# RS_232.net
KiCad netlist of a schematic drawn in Altium Designer
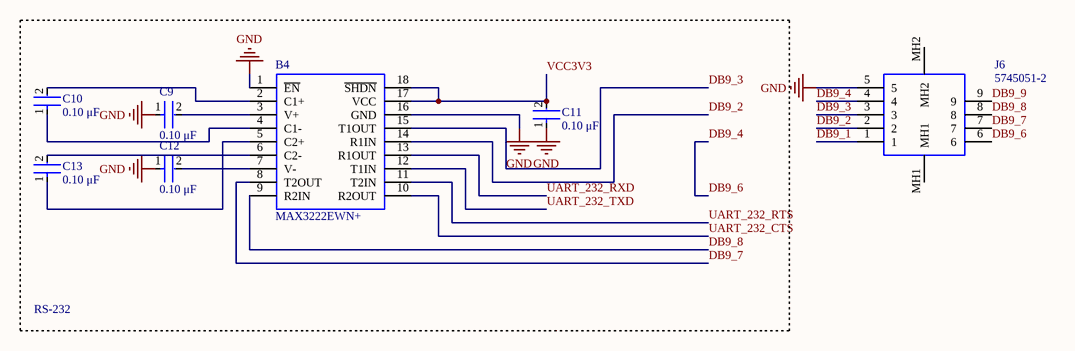
[diagram p0: RS_232.SchDoc]

(export (version "E")
  (design (tool "Eeschema 10.0.6"))
  (components
    (comp (ref "B4")
      (value "MAX3222EWN+")
      (footprint "SOIC127P1032X265-18N")
      (fields (field (name "MOUSER PART NUMBER") "700-MAX3222EWN"))
      (libsource (lib "Schlib2") (part "MAX3222EWN+"))
    )
    (comp (ref "C9")
      (value "0.10 μF")
      (footprint "FP-C0805C-DN-MFG")
      (description "C0805 0.10 μF X7R 30ppm/°C 10.00% 50 V")
      (fields
        (field (name "MANUFACTURER") "KEMET")
        (field (name "MANUFACTURER PART NUMBER") "C0805C104K5RAC7411")
      )
      (libsource (lib "Altium Content Vault") (part "b4654b650e69147ec39a6b967a45e02"))
    )
    (comp (ref "C10")
      (value "0.10 μF")
      (footprint "FP-C0805C-DN-MFG")
      (description "C0805 0.10 μF X7R 30ppm/°C 10.00% 50 V")
      (fields
        (field (name "MANUFACTURER") "KEMET")
        (field (name "MANUFACTURER PART NUMBER") "C0805C104K5RAC7411")
      )
      (libsource (lib "Altium Content Vault") (part "b4654b650e69147ec39a6b967a45e02"))
    )
    (comp (ref "C11")
      (value "0.10 μF")
      (footprint "FP-C0805C-DN-MFG")
      (description "C0805 0.10 μF X7R 30ppm/°C 10.00% 50 V")
      (fields
        (field (name "MANUFACTURER") "KEMET")
        (field (name "MANUFACTURER PART NUMBER") "C0805C104K5RAC7411")
      )
      (libsource (lib "Altium Content Vault") (part "b4654b650e69147ec39a6b967a45e02"))
    )
    (comp (ref "C12")
      (value "0.10 μF")
      (footprint "FP-C0805C-DN-MFG")
      (description "C0805 0.10 μF X7R 30ppm/°C 10.00% 50 V")
      (fields
        (field (name "MANUFACTURER") "KEMET")
        (field (name "MANUFACTURER PART NUMBER") "C0805C104K5RAC7411")
      )
      (libsource (lib "Altium Content Vault") (part "b4654b650e69147ec39a6b967a45e02"))
    )
    (comp (ref "C13")
      (value "0.10 μF")
      (footprint "FP-C0805C-DN-MFG")
      (description "C0805 0.10 μF X7R 30ppm/°C 10.00% 50 V")
      (fields
        (field (name "MANUFACTURER") "KEMET")
        (field (name "MANUFACTURER PART NUMBER") "C0805C104K5RAC7411")
      )
      (libsource (lib "Altium Content Vault") (part "b4654b650e69147ec39a6b967a45e02"))
    )
    (comp (ref "J6")
      (value "5745051-2")
      (footprint "57450512")
      (description "HD-20 PLUG 9P VERT THD INS")
      (fields (field (name "MOUSER PART NUMBER") "571-5745051-2"))
      (libsource (lib "Schlib2") (part "5745051-2"))
    )
  )
  (nets
    (net (code "1") (name "/DB9_1") (class "Default")
      (node (ref "J6") (pin "1") (pinfunction "1_1") (pintype "passive"))
    )
    (net (code "2") (name "/DB9_2") (class "Default")
      (node (ref "B4") (pin "14") (pinfunction "R1IN_14") (pintype "passive"))
      (node (ref "J6") (pin "2") (pinfunction "2_2") (pintype "passive"))
    )
    (net (code "3") (name "/DB9_3") (class "Default")
      (node (ref "B4") (pin "15") (pinfunction "T1OUT_15") (pintype "passive"))
      (node (ref "J6") (pin "3") (pinfunction "3_3") (pintype "passive"))
    )
    (net (code "4") (name "/DB9_4") (class "Default")
      (node (ref "J6") (pin "4") (pinfunction "4_4") (pintype "passive"))
      (node (ref "J6") (pin "6") (pinfunction "6_6") (pintype "passive"))
    )
    (net (code "5") (name "/DB9_7") (class "Default")
      (node (ref "B4") (pin "8") (pinfunction "T2OUT_8") (pintype "passive"))
      (node (ref "J6") (pin "7") (pinfunction "7_7") (pintype "passive"))
    )
    (net (code "6") (name "/DB9_8") (class "Default")
      (node (ref "B4") (pin "9") (pinfunction "R2IN_9") (pintype "passive"))
      (node (ref "J6") (pin "8") (pinfunction "8_8") (pintype "passive"))
    )
    (net (code "7") (name "/DB9_9") (class "Default")
      (node (ref "J6") (pin "9") (pinfunction "9_9") (pintype "passive"))
    )
    (net (code "8") (name "/UART_232_CTS") (class "Default")
      (node (ref "B4") (pin "10") (pinfunction "R2OUT_10") (pintype "passive"))
    )
    (net (code "9") (name "/UART_232_RTS") (class "Default")
      (node (ref "B4") (pin "11") (pinfunction "T2IN_11") (pintype "passive"))
    )
    (net (code "10") (name "/UART_232_RXD") (class "Default")
      (node (ref "B4") (pin "13") (pinfunction "R1OUT_13") (pintype "passive"))
    )
    (net (code "11") (name "/UART_232_TXD") (class "Default")
      (node (ref "B4") (pin "12") (pinfunction "T1IN_12") (pintype "passive"))
    )
    (net (code "12") (name "/VCC3V3") (class "Default")
      (node (ref "B4") (pin "17") (pinfunction "VCC_17") (pintype "passive"))
      (node (ref "B4") (pin "18") (pinfunction "SHDN_18") (pintype "passive"))
      (node (ref "C11") (pin "2") (pinfunction "2_2") (pintype "passive"))
    )
    (net (code "13") (name "GND") (class "Default")
      (node (ref "B4") (pin "1") (pinfunction "EN_1") (pintype "passive"))
      (node (ref "B4") (pin "16") (pinfunction "GND_16") (pintype "passive"))
      (node (ref "C11") (pin "1") (pinfunction "1_1") (pintype "passive"))
      (node (ref "C12") (pin "1") (pinfunction "1_1") (pintype "passive"))
      (node (ref "C9") (pin "1") (pinfunction "1_1") (pintype "passive"))
      (node (ref "J6") (pin "5") (pinfunction "5_5") (pintype "passive"))
    )
    (net (code "14") (name "Net-(B4-C1+)") (class "Default")
      (node (ref "B4") (pin "2") (pinfunction "C1+_2") (pintype "passive"))
      (node (ref "C10") (pin "2") (pinfunction "2_2") (pintype "passive"))
    )
    (net (code "15") (name "Net-(B4-C1-)") (class "Default")
      (node (ref "B4") (pin "4") (pinfunction "C1-_4") (pintype "passive"))
      (node (ref "C10") (pin "1") (pinfunction "1_1") (pintype "passive"))
    )
    (net (code "16") (name "Net-(B4-C2+)") (class "Default")
      (node (ref "B4") (pin "5") (pinfunction "C2+_5") (pintype "passive"))
      (node (ref "C13") (pin "1") (pinfunction "1_1") (pintype "passive"))
    )
    (net (code "17") (name "Net-(B4-C2-)") (class "Default")
      (node (ref "B4") (pin "6") (pinfunction "C2-_6") (pintype "passive"))
      (node (ref "C13") (pin "2") (pinfunction "2_2") (pintype "passive"))
    )
    (net (code "18") (name "Net-(B4-V+)") (class "Default")
      (node (ref "B4") (pin "3") (pinfunction "V+_3") (pintype "passive"))
      (node (ref "C9") (pin "2") (pinfunction "2_2") (pintype "passive"))
    )
    (net (code "19") (name "Net-(B4-V-)") (class "Default")
      (node (ref "B4") (pin "7") (pinfunction "V-_7") (pintype "passive"))
      (node (ref "C12") (pin "2") (pinfunction "2_2") (pintype "passive"))
    )
    (net (code "20") (name "unconnected-(J6-PadMH1)") (class "Default")
      (node (ref "J6") (pin "MH1") (pinfunction "MH1_MH1") (pintype "passive"))
    )
    (net (code "21") (name "unconnected-(J6-PadMH2)") (class "Default")
      (node (ref "J6") (pin "MH2") (pinfunction "MH2_MH2") (pintype "passive"))
    )
  )
)
